# Driving_Circuit_one.net
KiCad netlist of a schematic drawn in Altium Designer
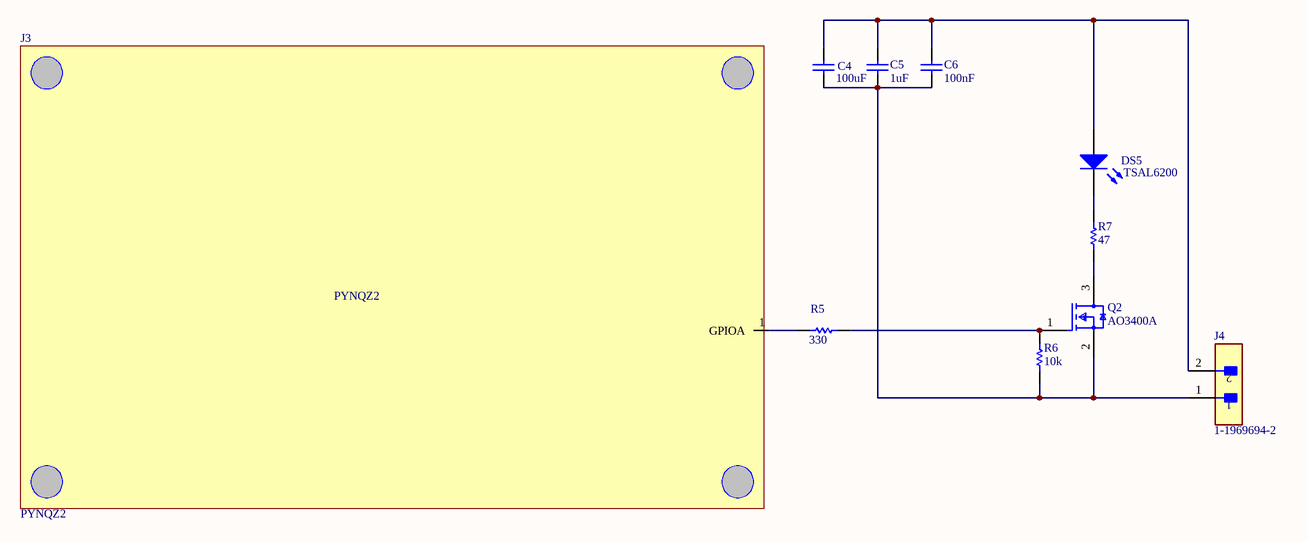
[diagram p0: Driving_Circuit_one.SchDoc]

(export (version "E")
  (design (tool "Eeschema 10.0.6"))
  (components
    (comp (ref "C4")
      (value "100uF")
      (footprint "CAPC2013X145X48ML20T23")
      (fields (field (name "MANUFACTURER") "Vitramon") (field (name "PART NUMBER") "VJ0805Y682KXAMT"))
      (libsource (lib "Altium Content Vault") (part "CAP"))
    )
    (comp (ref "C5")
      (value "1uF")
      (footprint "CAPC2013X145X48ML20T23")
      (fields (field (name "MANUFACTURER") "Vitramon") (field (name "PART NUMBER") "VJ0805Y682KXAMT"))
      (libsource (lib "Altium Content Vault") (part "CAP"))
    )
    (comp (ref "C6")
      (value "100nF")
      (footprint "CAPC2013X145X48ML20T23")
      (fields (field (name "MANUFACTURER") "Vitramon") (field (name "PART NUMBER") "VJ0805Y682KXAMT"))
      (libsource (lib "Altium Content Vault") (part "CAP"))
    )
    (comp (ref "DS5")
      (value "TSAL6200")
      (footprint "VISH-TSAL6200")
      (fields (field (name "MANUFACTURER") "Vishay"))
      (libsource (lib "Altium Content Vault") (part "LED-AK-2"))
    )
    (comp (ref "J3") (value "PYNQZ2") (footprint "PYNQZ2_board") (libsource (lib "Schlib1") (part "PYNQZ2")))
    (comp (ref "J4")
      (value "1-1969694-2")
      (footprint "FP-1-1969694-2-MFG")
      (description "CONN HEADER R/A 2POS 6MM")
      (libsource (lib "Altium Content Vault") (part "3bc925449376181038e59eaffc5286c"))
    )
    (comp (ref "Q2")
      (value "AO3400A")
      (footprint "FP-SOT23-MFG")
      (description "MOSFET N-CH 30V 5.7A SOT23")
      (libsource (lib "Altium Content Vault") (part "0a9ea7c96deaaede766a5b531c28de0"))
    )
    (comp (ref "R5")
      (value "330")
      (footprint "RESC3116X65X40LL10T20")
      (fields (field (name "PART NUMBER") "RC1206FR-10750RL") (field (name "MANUFACTURER") "Yageo"))
      (libsource (lib "Altium Content Vault") (part "RES"))
    )
    (comp (ref "R6")
      (value "10k")
      (footprint "RESC3116X65X40LL10T20")
      (fields (field (name "PART NUMBER") "RC1206FR-10750RL") (field (name "MANUFACTURER") "Yageo"))
      (libsource (lib "Altium Content Vault") (part "RES"))
    )
    (comp (ref "R7")
      (value "47")
      (footprint "RESC3116X65X40LL10T20")
      (fields (field (name "PART NUMBER") "RC1206FR-10750RL") (field (name "MANUFACTURER") "Yageo"))
      (libsource (lib "Altium Content Vault") (part "RES"))
    )
  )
  (nets
    (net (code "1") (name "Net-(DS5-A)") (class "Default")
      (node (ref "C4") (pin "2") (pinfunction "2_2") (pintype "passive"))
      (node (ref "C5") (pin "2") (pinfunction "2_2") (pintype "passive"))
      (node (ref "C6") (pin "2") (pinfunction "2_2") (pintype "passive"))
      (node (ref "DS5") (pin "1") (pinfunction "A_1") (pintype "passive"))
      (node (ref "J4") (pin "2") (pinfunction "2_2") (pintype "passive"))
    )
    (net (code "2") (name "Net-(DS5-K)") (class "Default")
      (node (ref "DS5") (pin "2") (pinfunction "K_2") (pintype "passive"))
      (node (ref "R7") (pin "2") (pinfunction "2_2") (pintype "passive"))
    )
    (net (code "3") (name "Net-(J3-GPIOA)") (class "Default")
      (node (ref "J3") (pin "1") (pinfunction "GPIOA_1") (pintype "passive"))
      (node (ref "R5") (pin "2") (pinfunction "2_2") (pintype "passive"))
    )
    (net (code "4") (name "Net-(Q2-D)") (class "Default")
      (node (ref "Q2") (pin "3") (pinfunction "D_3") (pintype "passive"))
      (node (ref "R7") (pin "1") (pinfunction "1_1") (pintype "passive"))
    )
    (net (code "5") (name "Net-(Q2-G)") (class "Default")
      (node (ref "Q2") (pin "1") (pinfunction "G_1") (pintype "passive"))
      (node (ref "R5") (pin "1") (pinfunction "1_1") (pintype "passive"))
      (node (ref "R6") (pin "2") (pinfunction "2_2") (pintype "passive"))
    )
    (net (code "6") (name "Net-(Q2-S)") (class "Default")
      (node (ref "C4") (pin "1") (pinfunction "1_1") (pintype "passive"))
      (node (ref "C5") (pin "1") (pinfunction "1_1") (pintype "passive"))
      (node (ref "C6") (pin "1") (pinfunction "1_1") (pintype "passive"))
      (node (ref "J4") (pin "1") (pinfunction "1_1") (pintype "passive"))
      (node (ref "Q2") (pin "2") (pinfunction "S_2") (pintype "passive"))
      (node (ref "R6") (pin "1") (pinfunction "1_1") (pintype "passive"))
    )
  )
)
